# 447Schematic.net
KiCad netlist of a schematic drawn in Altium Designer
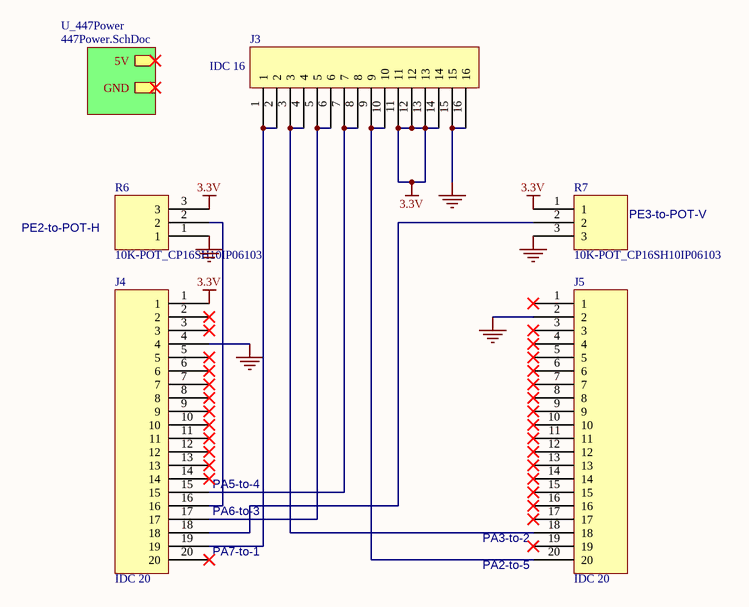
[diagram p0: 447Schematic.SchDoc]

(export (version "E")
  (design (tool "Eeschema 10.0.6"))
  (components
    (comp (ref "J3")
      (value "IDC 16")
      (footprint "IDC16")
      (description "IDC BOX HEADER .100\" 16POS")
      (fields
        (field (name "MANUFACTURER") "CNC Tech")
        (field (name "MANUFACTURER PART NUMBER") "3020-16-0100-00")
      )
      (libsource (lib "Schlib1") (part "3020-16-0100-00"))
    )
    (comp (ref "J4")
      (value "IDC 20")
      (footprint "IDC20")
      (description "IDC BOX HEADER .100\" 20POS")
      (fields
        (field (name "MANUFACTURER") "CNC Tech")
        (field (name "MANUFACTURER PART NUMBER") "3020-20-0100-00")
      )
      (libsource (lib "Schlib1") (part "3020-20-0100-00"))
    )
    (comp (ref "J5")
      (value "IDC 20")
      (footprint "IDC20")
      (description "IDC BOX HEADER .100\" 20POS")
      (fields
        (field (name "MANUFACTURER") "CNC Tech")
        (field (name "MANUFACTURER PART NUMBER") "3020-20-0100-00")
      )
      (libsource (lib "") (part "3020-20-0100-00_1"))
    )
    (comp (ref "R6")
      (value "10K-POT_CP16SH10IP06103")
      (footprint "POT (5mmPitch)")
      (description "POT 10K OHM 1/5W CARBON LINEAR")
      (fields
        (field (name "MANUFACTURER") "TE Connectivity Passive Product")
        (field (name "MANUFACTURER PART NUMBER") "CP16SH10IP06103")
      )
      (libsource (lib "") (part "CP16SH10IP06103_1"))
    )
    (comp (ref "R7")
      (value "10K-POT_CP16SH10IP06103")
      (footprint "POT (5mmPitch)")
      (description "POT 10K OHM 1/5W CARBON LINEAR")
      (fields
        (field (name "MANUFACTURER") "TE Connectivity Passive Product")
        (field (name "MANUFACTURER PART NUMBER") "CP16SH10IP06103")
      )
      (libsource (lib "Schlib1") (part "CP16SH10IP06103"))
    )
  )
  (nets
    (net (code "3") (name "3.3V") (class "Default")
      (node (ref "J3") (pin "11") (pinfunction "11_11") (pintype "passive"))
      (node (ref "J3") (pin "12") (pinfunction "12_12") (pintype "passive"))
      (node (ref "J3") (pin "13") (pinfunction "13_13") (pintype "passive"))
      (node (ref "J3") (pin "14") (pinfunction "14_14") (pintype "passive"))
      (node (ref "J4") (pin "1") (pinfunction "1_1") (pintype "passive"))
      (node (ref "R6") (pin "3") (pinfunction "3_3") (pintype "passive"))
      (node (ref "R7") (pin "1") (pinfunction "1_1") (pintype "passive"))
    )
    (net (code "4") (name "GND") (class "Default")
      (node (ref "J3") (pin "15") (pinfunction "15_15") (pintype "passive"))
      (node (ref "J3") (pin "16") (pinfunction "16_16") (pintype "passive"))
      (node (ref "J4") (pin "4") (pinfunction "4_4") (pintype "passive"))
      (node (ref "J5") (pin "2") (pinfunction "2_2") (pintype "passive"))
      (node (ref "R6") (pin "1") (pinfunction "1_1") (pintype "passive"))
      (node (ref "R7") (pin "3") (pinfunction "3_3") (pintype "passive"))
    )
    (net (code "5") (name "Net-(J3-Pad1)") (class "Default")
      (node (ref "J3") (pin "1") (pinfunction "1_1") (pintype "passive"))
      (node (ref "J3") (pin "2") (pinfunction "2_2") (pintype "passive"))
      (node (ref "J4") (pin "19") (pinfunction "19_19") (pintype "passive"))
    )
    (net (code "6") (name "Net-(J3-Pad3)") (class "Default")
      (node (ref "J3") (pin "3") (pinfunction "3_3") (pintype "passive"))
      (node (ref "J3") (pin "4") (pinfunction "4_4") (pintype "passive"))
      (node (ref "J5") (pin "18") (pinfunction "18_18") (pintype "passive"))
    )
    (net (code "7") (name "Net-(J3-Pad5)") (class "Default")
      (node (ref "J3") (pin "5") (pinfunction "5_5") (pintype "passive"))
      (node (ref "J3") (pin "6") (pinfunction "6_6") (pintype "passive"))
      (node (ref "J4") (pin "17") (pinfunction "17_17") (pintype "passive"))
    )
    (net (code "8") (name "Net-(J3-Pad7)") (class "Default")
      (node (ref "J3") (pin "7") (pinfunction "7_7") (pintype "passive"))
      (node (ref "J3") (pin "8") (pinfunction "8_8") (pintype "passive"))
      (node (ref "J4") (pin "15") (pinfunction "15_15") (pintype "passive"))
    )
    (net (code "9") (name "Net-(J3-Pad10)") (class "Default")
      (node (ref "J3") (pin "10") (pinfunction "10_10") (pintype "passive"))
      (node (ref "J3") (pin "9") (pinfunction "9_9") (pintype "passive"))
      (node (ref "J5") (pin "20") (pinfunction "20_20") (pintype "passive"))
    )
    (net (code "10") (name "Net-(J4-Pad16)") (class "Default")
      (node (ref "J4") (pin "16") (pinfunction "16_16") (pintype "passive"))
      (node (ref "R6") (pin "2") (pinfunction "2_2") (pintype "passive"))
    )
    (net (code "11") (name "Net-(J4-Pad18)") (class "Default")
      (node (ref "J4") (pin "18") (pinfunction "18_18") (pintype "passive"))
      (node (ref "R7") (pin "2") (pinfunction "2_2") (pintype "passive"))
    )
    (net (code "12") (name "unconnected-(J4-Pad2)") (class "Default")
      (node (ref "J4") (pin "2") (pinfunction "2_2") (pintype "passive+no_connect"))
    )
    (net (code "13") (name "unconnected-(J4-Pad3)") (class "Default")
      (node (ref "J4") (pin "3") (pinfunction "3_3") (pintype "passive+no_connect"))
    )
    (net (code "14") (name "unconnected-(J4-Pad5)") (class "Default")
      (node (ref "J4") (pin "5") (pinfunction "5_5") (pintype "passive+no_connect"))
    )
    (net (code "15") (name "unconnected-(J4-Pad6)") (class "Default")
      (node (ref "J4") (pin "6") (pinfunction "6_6") (pintype "passive+no_connect"))
    )
    (net (code "16") (name "unconnected-(J4-Pad7)") (class "Default")
      (node (ref "J4") (pin "7") (pinfunction "7_7") (pintype "passive+no_connect"))
    )
    (net (code "17") (name "unconnected-(J4-Pad8)") (class "Default")
      (node (ref "J4") (pin "8") (pinfunction "8_8") (pintype "passive+no_connect"))
    )
    (net (code "18") (name "unconnected-(J4-Pad9)") (class "Default")
      (node (ref "J4") (pin "9") (pinfunction "9_9") (pintype "passive+no_connect"))
    )
    (net (code "19") (name "unconnected-(J4-Pad10)") (class "Default")
      (node (ref "J4") (pin "10") (pinfunction "10_10") (pintype "passive+no_connect"))
    )
    (net (code "20") (name "unconnected-(J4-Pad11)") (class "Default")
      (node (ref "J4") (pin "11") (pinfunction "11_11") (pintype "passive+no_connect"))
    )
    (net (code "21") (name "unconnected-(J4-Pad12)") (class "Default")
      (node (ref "J4") (pin "12") (pinfunction "12_12") (pintype "passive+no_connect"))
    )
    (net (code "22") (name "unconnected-(J4-Pad13)") (class "Default")
      (node (ref "J4") (pin "13") (pinfunction "13_13") (pintype "passive+no_connect"))
    )
    (net (code "23") (name "unconnected-(J4-Pad14)") (class "Default")
      (node (ref "J4") (pin "14") (pinfunction "14_14") (pintype "passive+no_connect"))
    )
    (net (code "24") (name "unconnected-(J4-Pad20)") (class "Default")
      (node (ref "J4") (pin "20") (pinfunction "20_20") (pintype "passive+no_connect"))
    )
    (net (code "25") (name "unconnected-(J5-Pad1)") (class "Default")
      (node (ref "J5") (pin "1") (pinfunction "1_1") (pintype "passive+no_connect"))
    )
    (net (code "26") (name "unconnected-(J5-Pad3)") (class "Default")
      (node (ref "J5") (pin "3") (pinfunction "3_3") (pintype "passive+no_connect"))
    )
    (net (code "27") (name "unconnected-(J5-Pad4)") (class "Default")
      (node (ref "J5") (pin "4") (pinfunction "4_4") (pintype "passive+no_connect"))
    )
    (net (code "28") (name "unconnected-(J5-Pad5)") (class "Default")
      (node (ref "J5") (pin "5") (pinfunction "5_5") (pintype "passive+no_connect"))
    )
    (net (code "29") (name "unconnected-(J5-Pad6)") (class "Default")
      (node (ref "J5") (pin "6") (pinfunction "6_6") (pintype "passive+no_connect"))
    )
    (net (code "30") (name "unconnected-(J5-Pad7)") (class "Default")
      (node (ref "J5") (pin "7") (pinfunction "7_7") (pintype "passive+no_connect"))
    )
    (net (code "31") (name "unconnected-(J5-Pad8)") (class "Default")
      (node (ref "J5") (pin "8") (pinfunction "8_8") (pintype "passive+no_connect"))
    )
    (net (code "32") (name "unconnected-(J5-Pad9)") (class "Default")
      (node (ref "J5") (pin "9") (pinfunction "9_9") (pintype "passive+no_connect"))
    )
    (net (code "33") (name "unconnected-(J5-Pad10)") (class "Default")
      (node (ref "J5") (pin "10") (pinfunction "10_10") (pintype "passive+no_connect"))
    )
    (net (code "34") (name "unconnected-(J5-Pad11)") (class "Default")
      (node (ref "J5") (pin "11") (pinfunction "11_11") (pintype "passive+no_connect"))
    )
    (net (code "35") (name "unconnected-(J5-Pad12)") (class "Default")
      (node (ref "J5") (pin "12") (pinfunction "12_12") (pintype "passive+no_connect"))
    )
    (net (code "36") (name "unconnected-(J5-Pad13)") (class "Default")
      (node (ref "J5") (pin "13") (pinfunction "13_13") (pintype "passive+no_connect"))
    )
    (net (code "37") (name "unconnected-(J5-Pad14)") (class "Default")
      (node (ref "J5") (pin "14") (pinfunction "14_14") (pintype "passive+no_connect"))
    )
    (net (code "38") (name "unconnected-(J5-Pad15)") (class "Default")
      (node (ref "J5") (pin "15") (pinfunction "15_15") (pintype "passive+no_connect"))
    )
    (net (code "39") (name "unconnected-(J5-Pad16)") (class "Default")
      (node (ref "J5") (pin "16") (pinfunction "16_16") (pintype "passive+no_connect"))
    )
    (net (code "40") (name "unconnected-(J5-Pad17)") (class "Default")
      (node (ref "J5") (pin "17") (pinfunction "17_17") (pintype "passive+no_connect"))
    )
    (net (code "41") (name "unconnected-(J5-Pad19)") (class "Default")
      (node (ref "J5") (pin "19") (pinfunction "19_19") (pintype "passive+no_connect"))
    )
  )
)
